# RS485_ISO_Sensor_unit.net
KiCad netlist of a schematic drawn in EAGLE
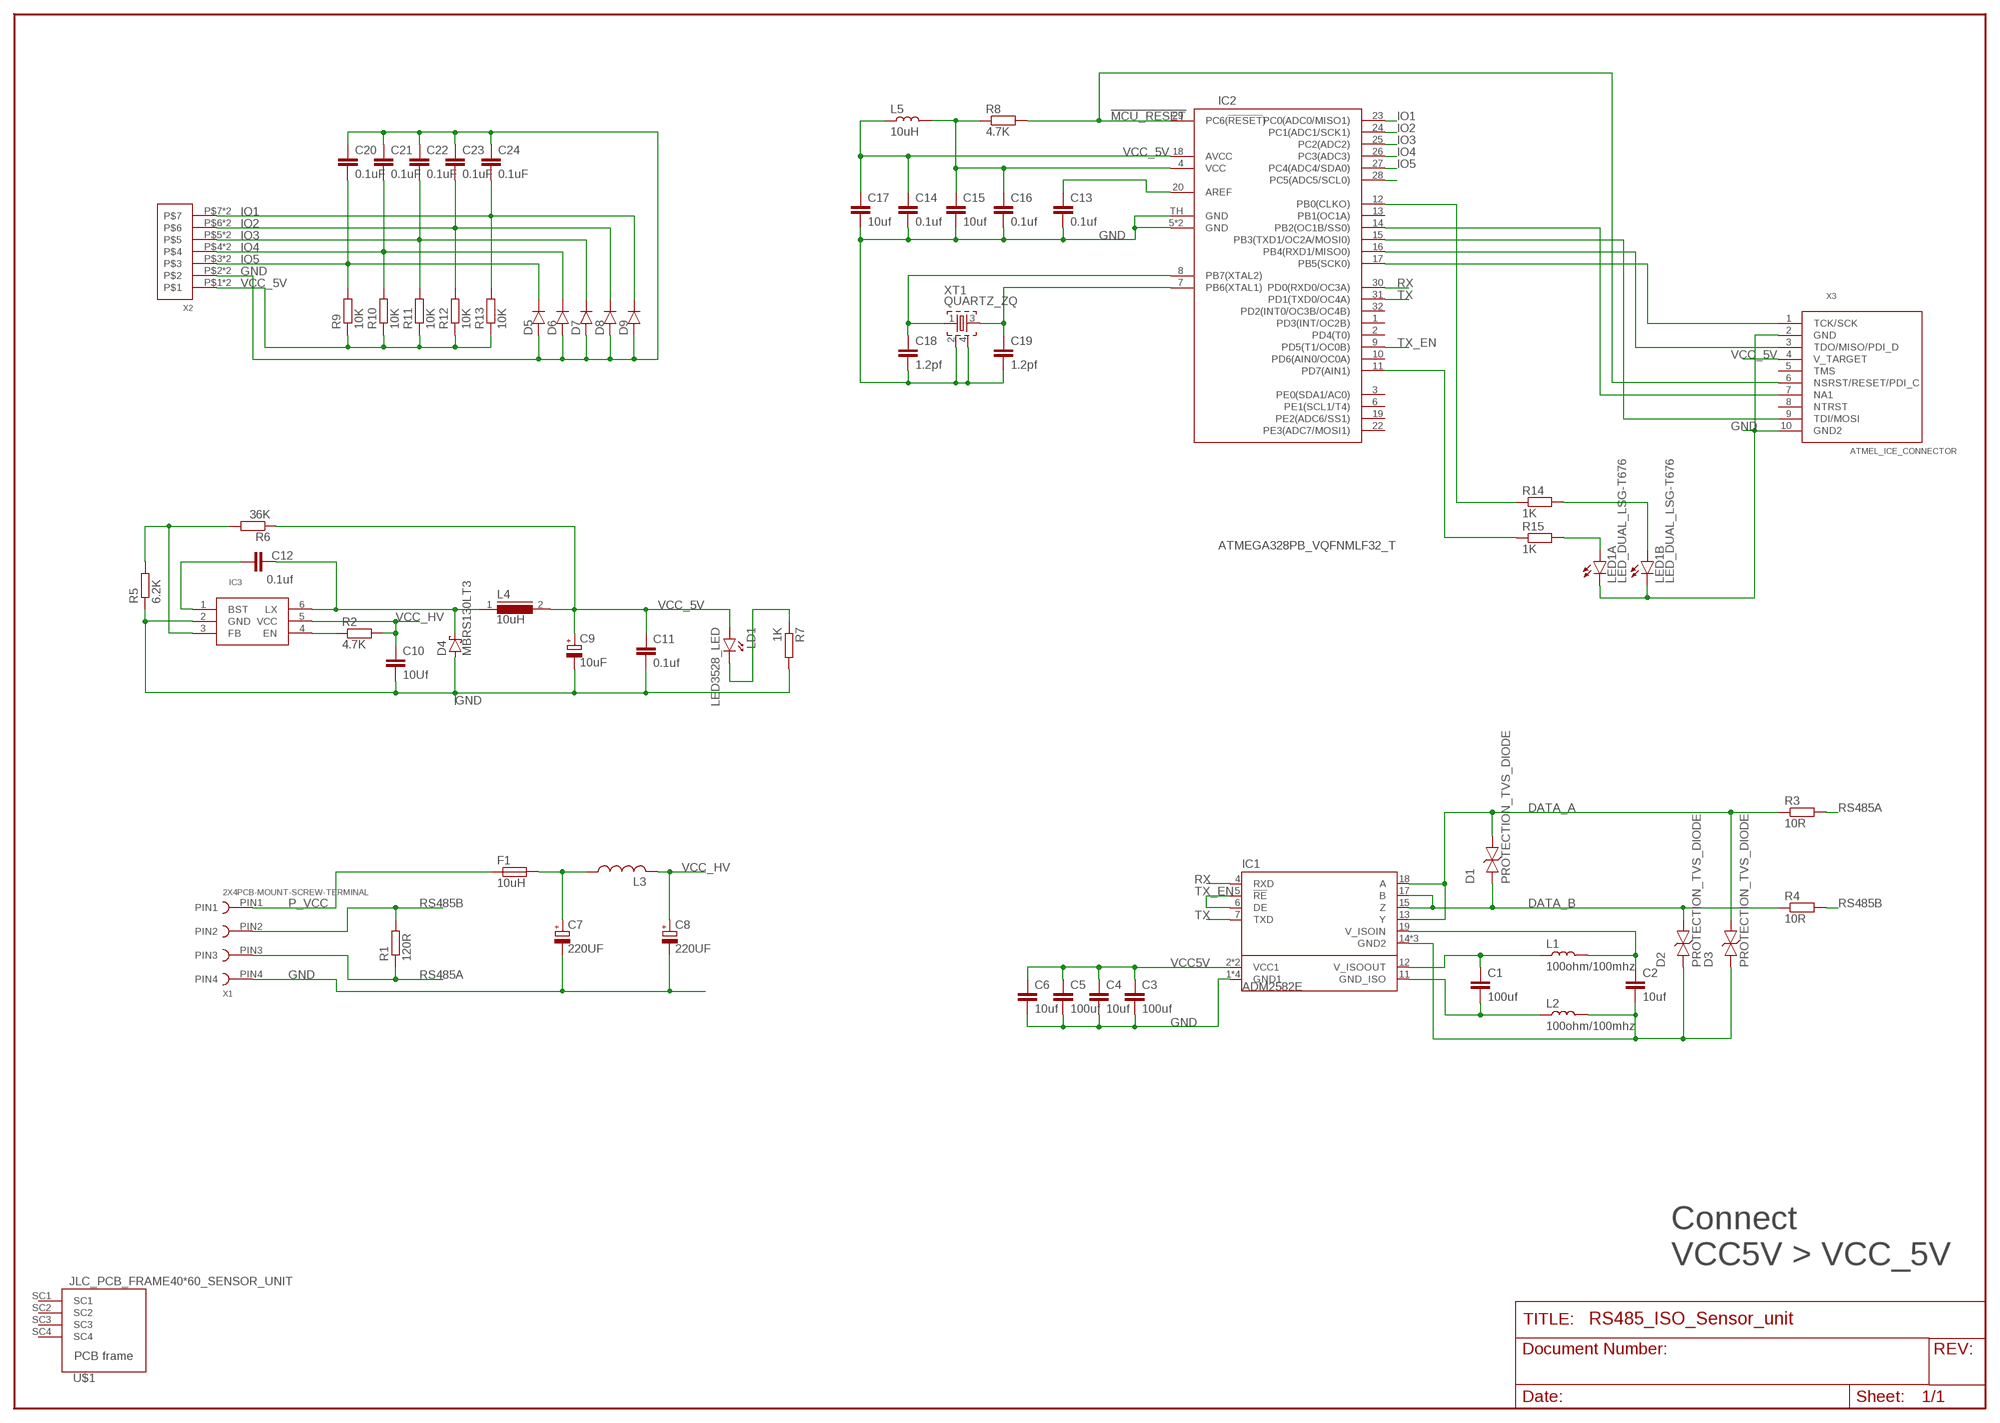
[diagram p0: schematic, sheet 1]

(export (version "E")
  (design (tool "Eeschema 10.0.6"))
  (components
    (comp (ref "C1")
      (value "100uf")
      (footprint "eagle-import:0603")
      (libsource (lib "eagle-import") (part "SMD_C0603"))
    )
    (comp (ref "C2")
      (value "10uf")
      (footprint "eagle-import:0603")
      (libsource (lib "eagle-import") (part "SMD_C0603"))
    )
    (comp (ref "C3")
      (value "100uf")
      (footprint "eagle-import:0603")
      (libsource (lib "eagle-import") (part "SMD_C0603"))
    )
    (comp (ref "C4")
      (value "10uf")
      (footprint "eagle-import:0603")
      (libsource (lib "eagle-import") (part "SMD_C0603"))
    )
    (comp (ref "C5")
      (value "100uf")
      (footprint "eagle-import:0603")
      (libsource (lib "eagle-import") (part "SMD_C0603"))
    )
    (comp (ref "C6")
      (value "10uf")
      (footprint "eagle-import:0603")
      (libsource (lib "eagle-import") (part "SMD_C0603"))
    )
    (comp (ref "C7")
      (value "220UF")
      (footprint "eagle-import:3.6MM")
      (libsource (lib "eagle-import") (part "RADIAL_330UF_25V_8MM"))
    )
    (comp (ref "C8")
      (value "220UF")
      (footprint "eagle-import:3.6MM")
      (libsource (lib "eagle-import") (part "RADIAL_330UF_25V_8MM"))
    )
    (comp (ref "C9")
      (value "10uF")
      (footprint "eagle-import:D_7343-31R")
      (libsource (lib "eagle-import") (part "TANTAL_686_7343"))
    )
    (comp (ref "C10")
      (value "10Uf")
      (footprint "eagle-import:1206")
      (libsource (lib "eagle-import") (part "SMD_C1206"))
    )
    (comp (ref "C11")
      (value "0.1uf")
      (footprint "eagle-import:0603")
      (libsource (lib "eagle-import") (part "SMD_C0603"))
    )
    (comp (ref "C12")
      (value "0.1uf")
      (footprint "eagle-import:0603")
      (libsource (lib "eagle-import") (part "SMD_C0603"))
    )
    (comp (ref "C13")
      (value "0.1uf")
      (footprint "eagle-import:0603")
      (libsource (lib "eagle-import") (part "SMD_C0603"))
    )
    (comp (ref "C14")
      (value "0.1uf")
      (footprint "eagle-import:0603")
      (libsource (lib "eagle-import") (part "SMD_C0603"))
    )
    (comp (ref "C15")
      (value "10uf")
      (footprint "eagle-import:3528")
      (libsource (lib "eagle-import") (part "SMD_C3528"))
    )
    (comp (ref "C16")
      (value "0.1uf")
      (footprint "eagle-import:0603")
      (libsource (lib "eagle-import") (part "SMD_C0603"))
    )
    (comp (ref "C17")
      (value "10uf")
      (footprint "eagle-import:3528")
      (libsource (lib "eagle-import") (part "SMD_C3528"))
    )
    (comp (ref "C18")
      (value "1.2pf")
      (footprint "eagle-import:0603")
      (libsource (lib "eagle-import") (part "SMD_C0603"))
    )
    (comp (ref "C19")
      (value "1.2pf")
      (footprint "eagle-import:0603")
      (libsource (lib "eagle-import") (part "SMD_C0603"))
    )
    (comp (ref "C20")
      (value "0.1uF")
      (footprint "eagle-import:0603")
      (libsource (lib "eagle-import") (part "SMD_C0603"))
    )
    (comp (ref "C21")
      (value "0.1uF")
      (footprint "eagle-import:0603")
      (libsource (lib "eagle-import") (part "SMD_C0603"))
    )
    (comp (ref "C22")
      (value "0.1uF")
      (footprint "eagle-import:0603")
      (libsource (lib "eagle-import") (part "SMD_C0603"))
    )
    (comp (ref "C23")
      (value "0.1uF")
      (footprint "eagle-import:0603")
      (libsource (lib "eagle-import") (part "SMD_C0603"))
    )
    (comp (ref "C24")
      (value "0.1uF")
      (footprint "eagle-import:0603")
      (libsource (lib "eagle-import") (part "SMD_C0603"))
    )
    (comp (ref "D1")
      (value "PROTECTION_TVS_DIODE")
      (footprint "eagle-import:SMA403D")
      (libsource (lib "eagle-import") (part "PROTECTION_TVS_DIODE"))
    )
    (comp (ref "D2")
      (value "PROTECTION_TVS_DIODE")
      (footprint "eagle-import:SMA403D")
      (libsource (lib "eagle-import") (part "PROTECTION_TVS_DIODE"))
    )
    (comp (ref "D3")
      (value "PROTECTION_TVS_DIODE")
      (footprint "eagle-import:SMA403D")
      (libsource (lib "eagle-import") (part "PROTECTION_TVS_DIODE"))
    )
    (comp (ref "D4")
      (value "MBRS130LT3")
      (footprint "eagle-import:SMB")
      (libsource (lib "eagle-import") (part "MBRS130LT3"))
    )
    (comp (ref "D5")
      (value "L1N4148WT1GSOD123_GALILE0_SMALL")
      (footprint "eagle-import:SOD-123_MINI-SMA")
      (libsource (lib "eagle-import") (part "L1N4148WT1GSOD123_GALILE0_SMALL"))
    )
    (comp (ref "D6")
      (value "L1N4148WT1GSOD123_GALILE0_SMALL")
      (footprint "eagle-import:SOD-123_MINI-SMA")
      (libsource (lib "eagle-import") (part "L1N4148WT1GSOD123_GALILE0_SMALL"))
    )
    (comp (ref "D7")
      (value "L1N4148WT1GSOD123_GALILE0_SMALL")
      (footprint "eagle-import:SOD-123_MINI-SMA")
      (libsource (lib "eagle-import") (part "L1N4148WT1GSOD123_GALILE0_SMALL"))
    )
    (comp (ref "D8")
      (value "L1N4148WT1GSOD123_GALILE0_SMALL")
      (footprint "eagle-import:SOD-123_MINI-SMA")
      (libsource (lib "eagle-import") (part "L1N4148WT1GSOD123_GALILE0_SMALL"))
    )
    (comp (ref "D9")
      (value "L1N4148WT1GSOD123_GALILE0_SMALL")
      (footprint "eagle-import:SOD-123_MINI-SMA")
      (libsource (lib "eagle-import") (part "L1N4148WT1GSOD123_GALILE0_SMALL"))
    )
    (comp (ref "F1")
      (value "10uH")
      (footprint "eagle-import:SMD_2410_FUSE_NOK")
      (libsource (lib "eagle-import") (part "SMD_FUSE"))
    )
    (comp (ref "IC1")
      (value "ADM2582E")
      (footprint "eagle-import:SO20L")
      (libsource (lib "eagle-import") (part "ADM2582E"))
    )
    (comp (ref "IC2")
      (value "ATMEGA328PB_VQFNMLF32_T")
      (footprint "eagle-import:MLF32-TH")
      (libsource (lib "eagle-import") (part "ATMEGA328PB_VQFNMLF32_T"))
    )
    (comp (ref "IC3")
      (value "BD9G101G_SOT23(6)")
      (footprint "eagle-import:SOT-23(6)")
      (libsource (lib "eagle-import") (part "BD9G101G_SOT23(6)"))
    )
    (comp (ref "L1")
      (value "100ohm/100mhz")
      (footprint "eagle-import:0805")
      (libsource (lib "eagle-import") (part "SMD_L"))
    )
    (comp (ref "L2")
      (value "100ohm/100mhz")
      (footprint "eagle-import:0805")
      (libsource (lib "eagle-import") (part "SMD_L"))
    )
    (comp (ref "L3")
      (value "L-US0207/2V")
      (footprint "eagle-import:0207_2V")
      (libsource (lib "eagle-import") (part "L-US0207/2V"))
    )
    (comp (ref "L4")
      (value "10uH")
      (footprint "eagle-import:DR74")
      (libsource (lib "eagle-import") (part "DR74"))
    )
    (comp (ref "L5")
      (value "10uH")
      (footprint "eagle-import:0805")
      (libsource (lib "eagle-import") (part "SMD_L"))
    )
    (comp (ref "LD1")
      (value "LED3528_LED")
      (footprint "eagle-import:3528")
      (libsource (lib "eagle-import") (part "LED3528_LED"))
    )
    (comp (ref "LED1")
      (value "LED_DUAL_LSG-T676")
      (footprint "eagle-import:P-LCC4-0")
      (libsource (lib "eagle-import") (part "LED_DUAL_LSG-T676"))
    )
    (comp (ref "R1")
      (value "120R")
      (footprint "eagle-import:0204_5")
      (libsource (lib "eagle-import") (part "R-EU_0204/5"))
    )
    (comp (ref "R2")
      (value "4.7K")
      (footprint "eagle-import:0603")
      (libsource (lib "eagle-import") (part "SMD_R0603"))
    )
    (comp (ref "R3")
      (value "10R")
      (footprint "eagle-import:1206")
      (libsource (lib "eagle-import") (part "SMD_R1206"))
    )
    (comp (ref "R4")
      (value "10R")
      (footprint "eagle-import:1206")
      (libsource (lib "eagle-import") (part "SMD_R1206"))
    )
    (comp (ref "R5")
      (value "6.2K")
      (footprint "eagle-import:0603")
      (libsource (lib "eagle-import") (part "SMD_R0603"))
    )
    (comp (ref "R6")
      (value "36K")
      (footprint "eagle-import:0603")
      (libsource (lib "eagle-import") (part "SMD_R0603"))
    )
    (comp (ref "R7")
      (value "1K")
      (footprint "eagle-import:0603")
      (libsource (lib "eagle-import") (part "SMD_R0603"))
    )
    (comp (ref "R8")
      (value "4.7K")
      (footprint "eagle-import:0603")
      (libsource (lib "eagle-import") (part "SMD_R0603"))
    )
    (comp (ref "R9")
      (value "10K")
      (footprint "eagle-import:0603")
      (libsource (lib "eagle-import") (part "SMD_R0603"))
    )
    (comp (ref "R10")
      (value "10K")
      (footprint "eagle-import:0603")
      (libsource (lib "eagle-import") (part "SMD_R0603"))
    )
    (comp (ref "R11")
      (value "10K")
      (footprint "eagle-import:0603")
      (libsource (lib "eagle-import") (part "SMD_R0603"))
    )
    (comp (ref "R12")
      (value "10K")
      (footprint "eagle-import:0603")
      (libsource (lib "eagle-import") (part "SMD_R0603"))
    )
    (comp (ref "R13")
      (value "10K")
      (footprint "eagle-import:0603")
      (libsource (lib "eagle-import") (part "SMD_R0603"))
    )
    (comp (ref "R14")
      (value "1K")
      (footprint "eagle-import:0603")
      (libsource (lib "eagle-import") (part "SMD_R0603"))
    )
    (comp (ref "R15")
      (value "1K")
      (footprint "eagle-import:0603")
      (libsource (lib "eagle-import") (part "SMD_R0603"))
    )
    (comp (ref "U$1")
      (value "JLC_PCB_FRAME40*60_SENSOR_UNIT")
      (footprint "eagle-import:40X60_SENSOR_UNIT")
      (libsource (lib "eagle-import") (part "JLC_PCB_FRAME4060_SENSOR_UNIT"))
    )
    (comp (ref "X1")
      (value "2X4PCB-MOUNT-SCREW-TERMINAL")
      (footprint "eagle-import:2X4PCB-MOUNT-SCREW-TERMINAL")
      (libsource (lib "eagle-import") (part "2X4PCB-MOUNT-SCREW-TERMINAL"))
    )
    (comp (ref "X2")
      (value "WAGO250_X7")
      (footprint "eagle-import:WAGO250_FP_7X")
      (libsource (lib "eagle-import") (part "WAGO250_X7"))
    )
    (comp (ref "X3")
      (value "ATMEL_ICE_CONNECTOR")
      (footprint "eagle-import:MINI10P_SPI_JTAG_PDI")
      (libsource (lib "eagle-import") (part "ATMEL_ICE_CONNECTOR"))
    )
    (comp (ref "XT1")
      (value "QUARTZ_ZQ")
      (footprint "eagle-import:QUARTZ_3X3MM")
      (libsource (lib "eagle-import") (part "QUARTZ_ZQ"))
    )
  )
  (nets
    (net (code "1") (name "/DATA_A") (class "Default")
      (node (ref "D1") (pin "P$2") (pinfunction "C_P$2") (pintype "bidirectional"))
      (node (ref "D3") (pin "P$2") (pinfunction "C_P$2") (pintype "bidirectional"))
      (node (ref "IC1") (pin "13") (pinfunction "Y_13") (pintype "bidirectional"))
      (node (ref "IC1") (pin "18") (pinfunction "A_18") (pintype "bidirectional"))
      (node (ref "R3") (pin "1") (pinfunction "1_1") (pintype "passive"))
    )
    (net (code "2") (name "/DATA_B") (class "Default")
      (node (ref "D1") (pin "P$1") (pinfunction "A_P$1") (pintype "bidirectional"))
      (node (ref "D2") (pin "P$2") (pinfunction "C_P$2") (pintype "bidirectional"))
      (node (ref "IC1") (pin "15") (pinfunction "Z_15") (pintype "bidirectional"))
      (node (ref "IC1") (pin "17") (pinfunction "B_17") (pintype "bidirectional"))
      (node (ref "R4") (pin "1") (pinfunction "1_1") (pintype "passive"))
    )
    (net (code "3") (name "/GND") (class "Default")
      (node (ref "C10") (pin "2") (pinfunction "2_2") (pintype "passive"))
      (node (ref "C11") (pin "2") (pinfunction "2_2") (pintype "passive"))
      (node (ref "C13") (pin "2") (pinfunction "2_2") (pintype "passive"))
      (node (ref "C14") (pin "2") (pinfunction "2_2") (pintype "passive"))
      (node (ref "C15") (pin "P") (pinfunction "2_P") (pintype "passive"))
      (node (ref "C16") (pin "2") (pinfunction "2_2") (pintype "passive"))
      (node (ref "C17") (pin "P") (pinfunction "2_P") (pintype "passive"))
      (node (ref "C18") (pin "2") (pinfunction "2_2") (pintype "passive"))
      (node (ref "C19") (pin "2") (pinfunction "2_2") (pintype "passive"))
      (node (ref "C20") (pin "1") (pinfunction "1_1") (pintype "passive"))
      (node (ref "C21") (pin "1") (pinfunction "1_1") (pintype "passive"))
      (node (ref "C22") (pin "1") (pinfunction "1_1") (pintype "passive"))
      (node (ref "C23") (pin "1") (pinfunction "1_1") (pintype "passive"))
      (node (ref "C24") (pin "1") (pinfunction "1_1") (pintype "passive"))
      (node (ref "C3") (pin "2") (pinfunction "2_2") (pintype "passive"))
      (node (ref "C4") (pin "2") (pinfunction "2_2") (pintype "passive"))
      (node (ref "C5") (pin "2") (pinfunction "2_2") (pintype "passive"))
      (node (ref "C6") (pin "2") (pinfunction "2_2") (pintype "passive"))
      (node (ref "C7") (pin "P$1") (pinfunction "-_P$1") (pintype "passive"))
      (node (ref "C8") (pin "P$1") (pinfunction "-_P$1") (pintype "passive"))
      (node (ref "C9") (pin "-") (pinfunction "-_-") (pintype "passive"))
      (node (ref "D4") (pin "A") (pinfunction "A_A") (pintype "passive"))
      (node (ref "D5") (pin "A") (pinfunction "A_A") (pintype "bidirectional"))
      (node (ref "D6") (pin "A") (pinfunction "A_A") (pintype "bidirectional"))
      (node (ref "D7") (pin "A") (pinfunction "A_A") (pintype "bidirectional"))
      (node (ref "D8") (pin "A") (pinfunction "A_A") (pintype "bidirectional"))
      (node (ref "D9") (pin "A") (pinfunction "A_A") (pintype "bidirectional"))
      (node (ref "IC1") (pin "1") (pinfunction "GND1_1") (pintype "bidirectional"))
      (node (ref "IC1") (pin "10") (pinfunction "GND1_10") (pintype "bidirectional"))
      (node (ref "IC1") (pin "3") (pinfunction "GND1_3") (pintype "bidirectional"))
      (node (ref "IC1") (pin "9") (pinfunction "GND1_9") (pintype "bidirectional"))
      (node (ref "IC2") (pin "21") (pinfunction "GND_21") (pintype "power_in"))
      (node (ref "IC2") (pin "5") (pinfunction "GND_5") (pintype "power_in"))
      (node (ref "IC2") (pin "TH") (pinfunction "GND_TH") (pintype "power_in"))
      (node (ref "IC3") (pin "2") (pinfunction "GND_2") (pintype "bidirectional"))
      (node (ref "LED1") (pin "1") (pinfunction "C_1") (pintype "passive"))
      (node (ref "LED1") (pin "3") (pinfunction "C_3") (pintype "passive"))
      (node (ref "R5") (pin "1") (pinfunction "1_1") (pintype "passive"))
      (node (ref "R7") (pin "2") (pinfunction "2_2") (pintype "passive"))
      (node (ref "X1") (pin "PIN4") (pinfunction "PIN4_PIN4") (pintype "bidirectional"))
      (node (ref "X2") (pin "P$2") (pinfunction "P$2_P$2") (pintype "bidirectional"))
      (node (ref "X2") (pin "U$2") (pinfunction "P$2_U$2") (pintype "bidirectional"))
      (node (ref "X3") (pin "10") (pinfunction "GND2_10") (pintype "bidirectional"))
      (node (ref "X3") (pin "2") (pinfunction "GND_2") (pintype "bidirectional"))
      (node (ref "XT1") (pin "2") (pinfunction "2_2") (pintype "passive"))
      (node (ref "XT1") (pin "4") (pinfunction "4_4") (pintype "passive"))
    )
    (net (code "4") (name "/IO1") (class "Default")
      (node (ref "C24") (pin "2") (pinfunction "2_2") (pintype "passive"))
      (node (ref "D9") (pin "C") (pinfunction "C_C") (pintype "bidirectional"))
      (node (ref "IC2") (pin "23") (pinfunction "PC0(ADC0/MISO1)_23") (pintype "bidirectional"))
      (node (ref "R13") (pin "2") (pinfunction "2_2") (pintype "passive"))
      (node (ref "X2") (pin "P$7") (pinfunction "P$7_P$7") (pintype "bidirectional"))
      (node (ref "X2") (pin "U$7") (pinfunction "P$7_U$7") (pintype "bidirectional"))
    )
    (net (code "5") (name "/IO2") (class "Default")
      (node (ref "C23") (pin "2") (pinfunction "2_2") (pintype "passive"))
      (node (ref "D8") (pin "C") (pinfunction "C_C") (pintype "bidirectional"))
      (node (ref "IC2") (pin "24") (pinfunction "PC1(ADC1/SCK1)_24") (pintype "bidirectional"))
      (node (ref "R12") (pin "2") (pinfunction "2_2") (pintype "passive"))
      (node (ref "X2") (pin "P$6") (pinfunction "P$6_P$6") (pintype "bidirectional"))
      (node (ref "X2") (pin "U$6") (pinfunction "P$6_U$6") (pintype "bidirectional"))
    )
    (net (code "6") (name "/IO3") (class "Default")
      (node (ref "C22") (pin "2") (pinfunction "2_2") (pintype "passive"))
      (node (ref "D7") (pin "C") (pinfunction "C_C") (pintype "bidirectional"))
      (node (ref "IC2") (pin "25") (pinfunction "PC2(ADC2)_25") (pintype "bidirectional"))
      (node (ref "R11") (pin "2") (pinfunction "2_2") (pintype "passive"))
      (node (ref "X2") (pin "P$5") (pinfunction "P$5_P$5") (pintype "bidirectional"))
      (node (ref "X2") (pin "U$5") (pinfunction "P$5_U$5") (pintype "bidirectional"))
    )
    (net (code "7") (name "/IO4") (class "Default")
      (node (ref "C21") (pin "2") (pinfunction "2_2") (pintype "passive"))
      (node (ref "D6") (pin "C") (pinfunction "C_C") (pintype "bidirectional"))
      (node (ref "IC2") (pin "26") (pinfunction "PC3(ADC3)_26") (pintype "bidirectional"))
      (node (ref "R10") (pin "2") (pinfunction "2_2") (pintype "passive"))
      (node (ref "X2") (pin "P$4") (pinfunction "P$4_P$4") (pintype "bidirectional"))
      (node (ref "X2") (pin "U$4") (pinfunction "P$4_U$4") (pintype "bidirectional"))
    )
    (net (code "8") (name "/IO5") (class "Default")
      (node (ref "C20") (pin "2") (pinfunction "2_2") (pintype "passive"))
      (node (ref "D5") (pin "C") (pinfunction "C_C") (pintype "bidirectional"))
      (node (ref "IC2") (pin "27") (pinfunction "PC4(ADC4/SDA0)_27") (pintype "bidirectional"))
      (node (ref "R9") (pin "2") (pinfunction "2_2") (pintype "passive"))
      (node (ref "X2") (pin "P$3") (pinfunction "P$3_P$3") (pintype "bidirectional"))
      (node (ref "X2") (pin "U$3") (pinfunction "P$3_U$3") (pintype "bidirectional"))
    )
    (net (code "9") (name "/P_VCC") (class "Default")
      (node (ref "F1") (pin "P$1") (pinfunction "1_P$1") (pintype "passive"))
      (node (ref "X1") (pin "PIN1") (pinfunction "PIN1_PIN1") (pintype "bidirectional"))
    )
    (net (code "10") (name "/RS485A") (class "Default")
      (node (ref "R1") (pin "1") (pinfunction "1_1") (pintype "passive"))
      (node (ref "R3") (pin "2") (pinfunction "2_2") (pintype "passive"))
      (node (ref "X1") (pin "PIN3") (pinfunction "PIN3_PIN3") (pintype "bidirectional"))
    )
    (net (code "11") (name "/RS485B") (class "Default")
      (node (ref "R1") (pin "2") (pinfunction "2_2") (pintype "passive"))
      (node (ref "R4") (pin "2") (pinfunction "2_2") (pintype "passive"))
      (node (ref "X1") (pin "PIN2") (pinfunction "PIN2_PIN2") (pintype "bidirectional"))
    )
    (net (code "12") (name "/RX") (class "Default")
      (node (ref "IC1") (pin "4") (pinfunction "RXD_4") (pintype "bidirectional"))
      (node (ref "IC2") (pin "30") (pinfunction "PD0(RXD0/OC3A)_30") (pintype "bidirectional"))
    )
    (net (code "13") (name "/TX") (class "Default")
      (node (ref "IC1") (pin "7") (pinfunction "TXD_7") (pintype "bidirectional"))
      (node (ref "IC2") (pin "31") (pinfunction "PD1(TXD0/OC4A)_31") (pintype "bidirectional"))
    )
    (net (code "14") (name "/TX_EN") (class "Default")
      (node (ref "IC1") (pin "5") (pinfunction "~{RE}_5") (pintype "bidirectional"))
      (node (ref "IC1") (pin "6") (pinfunction "DE_6") (pintype "bidirectional"))
      (node (ref "IC2") (pin "9") (pinfunction "PD5(T1/OC0B)_9") (pintype "bidirectional"))
    )
    (net (code "15") (name "/VCC5V") (class "Default")
      (node (ref "C3") (pin "1") (pinfunction "1_1") (pintype "passive"))
      (node (ref "C4") (pin "1") (pinfunction "1_1") (pintype "passive"))
      (node (ref "C5") (pin "1") (pinfunction "1_1") (pintype "passive"))
      (node (ref "C6") (pin "1") (pinfunction "1_1") (pintype "passive"))
      (node (ref "IC1") (pin "2") (pinfunction "VCC1_2") (pintype "bidirectional"))
      (node (ref "IC1") (pin "8") (pinfunction "VCC1_8") (pintype "bidirectional"))
    )
    (net (code "16") (name "/VCC_5V") (class "Default")
      (node (ref "C11") (pin "1") (pinfunction "1_1") (pintype "passive"))
      (node (ref "C15") (pin "M") (pinfunction "1_M") (pintype "passive"))
      (node (ref "C16") (pin "1") (pinfunction "1_1") (pintype "passive"))
      (node (ref "C9") (pin "+") (pinfunction "+_+") (pintype "passive"))
      (node (ref "IC2") (pin "4") (pinfunction "VCC_4") (pintype "power_in"))
      (node (ref "L4") (pin "2") (pinfunction "2_2") (pintype "passive"))
      (node (ref "L5") (pin "2") (pinfunction "2_2") (pintype "passive"))
      (node (ref "LD1") (pin "P") (pinfunction "A_P") (pintype "bidirectional"))
      (node (ref "R10") (pin "1") (pinfunction "1_1") (pintype "passive"))
      (node (ref "R11") (pin "1") (pinfunction "1_1") (pintype "passive"))
      (node (ref "R12") (pin "1") (pinfunction "1_1") (pintype "passive"))
      (node (ref "R13") (pin "1") (pinfunction "1_1") (pintype "passive"))
      (node (ref "R6") (pin "1") (pinfunction "1_1") (pintype "passive"))
      (node (ref "R8") (pin "1") (pinfunction "1_1") (pintype "passive"))
      (node (ref "R9") (pin "1") (pinfunction "1_1") (pintype "passive"))
      (node (ref "X2") (pin "P$1") (pinfunction "P$1_P$1") (pintype "bidirectional"))
      (node (ref "X2") (pin "U$1") (pinfunction "P$1_U$1") (pintype "bidirectional"))
      (node (ref "X3") (pin "4") (pinfunction "V_TARGET_4") (pintype "bidirectional"))
    )
    (net (code "17") (name "/VCC_HV") (class "Default")
      (node (ref "C10") (pin "1") (pinfunction "1_1") (pintype "passive"))
      (node (ref "C8") (pin "P$2") (pinfunction "+_P$2") (pintype "passive"))
      (node (ref "IC3") (pin "5") (pinfunction "VCC_5") (pintype "bidirectional"))
      (node (ref "L3") (pin "2") (pinfunction "2_2") (pintype "passive"))
      (node (ref "R2") (pin "2") (pinfunction "2_2") (pintype "passive"))
    )
    (net (code "18") (name "/~{MCU_RESET}") (class "Default")
      (node (ref "IC2") (pin "29") (pinfunction "PC6(~{RESET})_29") (pintype "bidirectional"))
      (node (ref "R8") (pin "2") (pinfunction "2_2") (pintype "passive"))
      (node (ref "X3") (pin "6") (pinfunction "NSRST/RESET/PDI_C_6") (pintype "bidirectional"))
    )
    (net (code "19") (name "Net-(C7-+)") (class "Default")
      (node (ref "C7") (pin "P$2") (pinfunction "+_P$2") (pintype "passive"))
      (node (ref "F1") (pin "P$2") (pinfunction "2_P$2") (pintype "passive"))
      (node (ref "L3") (pin "1") (pinfunction "1_1") (pintype "passive"))
    )
    (net (code "20") (name "Net-(C17-1)") (class "Default")
      (node (ref "C14") (pin "1") (pinfunction "1_1") (pintype "passive"))
      (node (ref "C17") (pin "M") (pinfunction "1_M") (pintype "passive"))
      (node (ref "IC2") (pin "18") (pinfunction "AVCC_18") (pintype "power_in"))
      (node (ref "L5") (pin "1") (pinfunction "1_1") (pintype "passive"))
    )
    (net (code "21") (name "Net-(D2-A)") (class "Default")
      (node (ref "C2") (pin "2") (pinfunction "2_2") (pintype "passive"))
      (node (ref "D2") (pin "P$1") (pinfunction "A_P$1") (pintype "bidirectional"))
      (node (ref "D3") (pin "P$1") (pinfunction "A_P$1") (pintype "bidirectional"))
      (node (ref "IC1") (pin "14") (pinfunction "GND2_14") (pintype "bidirectional"))
      (node (ref "IC1") (pin "16") (pinfunction "GND2_16") (pintype "bidirectional"))
      (node (ref "IC1") (pin "20") (pinfunction "GND2_20") (pintype "bidirectional"))
      (node (ref "L2") (pin "2") (pinfunction "2_2") (pintype "passive"))
    )
    (net (code "22") (name "Net-(IC1-GND_ISO)") (class "Default")
      (node (ref "C1") (pin "2") (pinfunction "2_2") (pintype "passive"))
      (node (ref "IC1") (pin "11") (pinfunction "GND_ISO_11") (pintype "bidirectional"))
      (node (ref "L2") (pin "1") (pinfunction "1_1") (pintype "passive"))
    )
    (net (code "23") (name "Net-(IC1-V_ISOIN)") (class "Default")
      (node (ref "C2") (pin "1") (pinfunction "1_1") (pintype "passive"))
      (node (ref "IC1") (pin "19") (pinfunction "V_ISOIN_19") (pintype "bidirectional"))
      (node (ref "L1") (pin "2") (pinfunction "2_2") (pintype "passive"))
    )
    (net (code "24") (name "Net-(IC1-V_ISOOUT)") (class "Default")
      (node (ref "C1") (pin "1") (pinfunction "1_1") (pintype "passive"))
      (node (ref "IC1") (pin "12") (pinfunction "V_ISOOUT_12") (pintype "bidirectional"))
      (node (ref "L1") (pin "1") (pinfunction "1_1") (pintype "passive"))
    )
    (net (code "25") (name "Net-(IC2-AREF)") (class "Default")
      (node (ref "C13") (pin "1") (pinfunction "1_1") (pintype "passive"))
      (node (ref "IC2") (pin "20") (pinfunction "AREF_20") (pintype "passive"))
    )
    (net (code "26") (name "Net-(IC2-PB0(CLKO))") (class "Default")
      (node (ref "IC2") (pin "12") (pinfunction "PB0(CLKO)_12") (pintype "bidirectional"))
      (node (ref "R14") (pin "1") (pinfunction "1_1") (pintype "passive"))
    )
    (net (code "27") (name "Net-(IC2-PB2(OC1B{slash}SS0))") (class "Default")
      (node (ref "IC2") (pin "14") (pinfunction "PB2(OC1B/SS0)_14") (pintype "bidirectional"))
      (node (ref "X3") (pin "7") (pinfunction "NA1_7") (pintype "bidirectional"))
    )
    (net (code "28") (name "Net-(IC2-PB3(TXD1{slash}OC2A{slash}MOSI0))") (class "Default")
      (node (ref "IC2") (pin "15") (pinfunction "PB3(TXD1/OC2A/MOSI0)_15") (pintype "bidirectional"))
      (node (ref "X3") (pin "9") (pinfunction "TDI/MOSI_9") (pintype "bidirectional"))
    )
    (net (code "29") (name "Net-(IC2-PB4(RXD1{slash}MISO0))") (class "Default")
      (node (ref "IC2") (pin "16") (pinfunction "PB4(RXD1/MISO0)_16") (pintype "bidirectional"))
      (node (ref "X3") (pin "3") (pinfunction "TDO/MISO/PDI_D_3") (pintype "bidirectional"))
    )
    (net (code "30") (name "Net-(IC2-PB5(SCK0))") (class "Default")
      (node (ref "IC2") (pin "17") (pinfunction "PB5(SCK0)_17") (pintype "bidirectional"))
      (node (ref "X3") (pin "1") (pinfunction "TCK/SCK_1") (pintype "bidirectional"))
    )
    (net (code "31") (name "Net-(IC2-PB6(XTAL1))") (class "Default")
      (node (ref "C19") (pin "1") (pinfunction "1_1") (pintype "passive"))
      (node (ref "IC2") (pin "7") (pinfunction "PB6(XTAL1)_7") (pintype "bidirectional"))
      (node (ref "XT1") (pin "3") (pinfunction "3_3") (pintype "passive"))
    )
    (net (code "32") (name "Net-(IC2-PB7(XTAL2))") (class "Default")
      (node (ref "C18") (pin "1") (pinfunction "1_1") (pintype "passive"))
      (node (ref "IC2") (pin "8") (pinfunction "PB7(XTAL2)_8") (pintype "bidirectional"))
      (node (ref "XT1") (pin "1") (pinfunction "1_1") (pintype "passive"))
    )
    (net (code "33") (name "Net-(IC2-PD7(AIN1))") (class "Default")
      (node (ref "IC2") (pin "11") (pinfunction "PD7(AIN1)_11") (pintype "bidirectional"))
      (node (ref "R15") (pin "1") (pinfunction "1_1") (pintype "passive"))
    )
    (net (code "34") (name "Net-(IC3-BST)") (class "Default")
      (node (ref "C12") (pin "1") (pinfunction "1_1") (pintype "passive"))
      (node (ref "IC3") (pin "1") (pinfunction "BST_1") (pintype "bidirectional"))
    )
    (net (code "35") (name "Net-(IC3-EN)") (class "Default")
      (node (ref "IC3") (pin "4") (pinfunction "EN_4") (pintype "bidirectional"))
      (node (ref "R2") (pin "1") (pinfunction "1_1") (pintype "passive"))
    )
    (net (code "36") (name "Net-(IC3-FB)") (class "Default")
      (node (ref "IC3") (pin "3") (pinfunction "FB_3") (pintype "bidirectional"))
      (node (ref "R5") (pin "2") (pinfunction "2_2") (pintype "passive"))
      (node (ref "R6") (pin "2") (pinfunction "2_2") (pintype "passive"))
    )
    (net (code "37") (name "Net-(IC3-LX)") (class "Default")
      (node (ref "C12") (pin "2") (pinfunction "2_2") (pintype "passive"))
      (node (ref "D4") (pin "C") (pinfunction "C_C") (pintype "passive"))
      (node (ref "IC3") (pin "6") (pinfunction "LX_6") (pintype "bidirectional"))
      (node (ref "L4") (pin "1") (pinfunction "1_1") (pintype "passive"))
    )
    (net (code "38") (name "Net-(LD1-K)") (class "Default")
      (node (ref "LD1") (pin "M") (pinfunction "K_M") (pintype "bidirectional"))
      (node (ref "R7") (pin "1") (pinfunction "1_1") (pintype "passive"))
    )
    (net (code "39") (name "Net-(LED1A-A)") (class "Default")
      (node (ref "LED1") (pin "2") (pinfunction "A_2") (pintype "passive"))
      (node (ref "R15") (pin "2") (pinfunction "2_2") (pintype "passive"))
    )
    (net (code "40") (name "Net-(LED1B-A)") (class "Default")
      (node (ref "LED1") (pin "4") (pinfunction "A_4") (pintype "passive"))
      (node (ref "R14") (pin "2") (pinfunction "2_2") (pintype "passive"))
    )
    (net (code "41") (name "unconnected-(IC2-PB1(OC1A)-Pad13)") (class "Default")
      (node (ref "IC2") (pin "13") (pinfunction "PB1(OC1A)_13") (pintype "bidirectional"))
    )
    (net (code "42") (name "unconnected-(IC2-PC5(ADC5{slash}SCL0)-Pad28)") (class "Default")
      (node (ref "IC2") (pin "28") (pinfunction "PC5(ADC5/SCL0)_28") (pintype "bidirectional"))
    )
    (net (code "43") (name "unconnected-(IC2-PD2(INT0{slash}OC3B{slash}OC4B)-Pad32)") (class "Default")
      (node (ref "IC2") (pin "32") (pinfunction "PD2(INT0/OC3B/OC4B)_32") (pintype "bidirectional"))
    )
    (net (code "44") (name "unconnected-(IC2-PD3(INT{slash}OC2B)-Pad1)") (class "Default")
      (node (ref "IC2") (pin "1") (pinfunction "PD3(INT/OC2B)_1") (pintype "bidirectional"))
    )
    (net (code "45") (name "unconnected-(IC2-PD4(T0)-Pad2)") (class "Default")
      (node (ref "IC2") (pin "2") (pinfunction "PD4(T0)_2") (pintype "bidirectional"))
    )
    (net (code "46") (name "unconnected-(IC2-PD6(AIN0{slash}OC0A)-Pad10)") (class "Default")
      (node (ref "IC2") (pin "10") (pinfunction "PD6(AIN0/OC0A)_10") (pintype "bidirectional"))
    )
    (net (code "47") (name "unconnected-(IC2-PE0(SDA1{slash}AC0)-Pad3)") (class "Default")
      (node (ref "IC2") (pin "3") (pinfunction "PE0(SDA1/AC0)_3") (pintype "bidirectional"))
    )
    (net (code "48") (name "unconnected-(IC2-PE1(SCL1{slash}T4)-Pad6)") (class "Default")
      (node (ref "IC2") (pin "6") (pinfunction "PE1(SCL1/T4)_6") (pintype "bidirectional"))
    )
    (net (code "49") (name "unconnected-(IC2-PE2(ADC6{slash}SS1)-Pad19)") (class "Default")
      (node (ref "IC2") (pin "19") (pinfunction "PE2(ADC6/SS1)_19") (pintype "bidirectional"))
    )
    (net (code "50") (name "unconnected-(IC2-PE3(ADC7{slash}MOSI1)-Pad22)") (class "Default")
      (node (ref "IC2") (pin "22") (pinfunction "PE3(ADC7/MOSI1)_22") (pintype "bidirectional"))
    )
    (net (code "51") (name "unconnected-(U$1-PadSC1)") (class "Default")
      (node (ref "U$1") (pin "SC1") (pinfunction "SC1_SC1") (pintype "bidirectional"))
    )
    (net (code "52") (name "unconnected-(U$1-PadSC2)") (class "Default")
      (node (ref "U$1") (pin "SC2") (pinfunction "SC2_SC2") (pintype "bidirectional"))
    )
    (net (code "53") (name "unconnected-(U$1-PadSC3)") (class "Default")
      (node (ref "U$1") (pin "SC3") (pinfunction "SC3_SC3") (pintype "bidirectional"))
    )
    (net (code "54") (name "unconnected-(U$1-PadSC4)") (class "Default")
      (node (ref "U$1") (pin "SC4") (pinfunction "SC4_SC4") (pintype "bidirectional"))
    )
    (net (code "55") (name "unconnected-(X3-NTRST-Pad8)") (class "Default")
      (node (ref "X3") (pin "8") (pinfunction "NTRST_8") (pintype "bidirectional"))
    )
    (net (code "56") (name "unconnected-(X3-TMS-Pad5)") (class "Default")
      (node (ref "X3") (pin "5") (pinfunction "TMS_5") (pintype "bidirectional"))
    )
  )
)
